# Adc.net
KiCad netlist of a schematic drawn in EAGLE
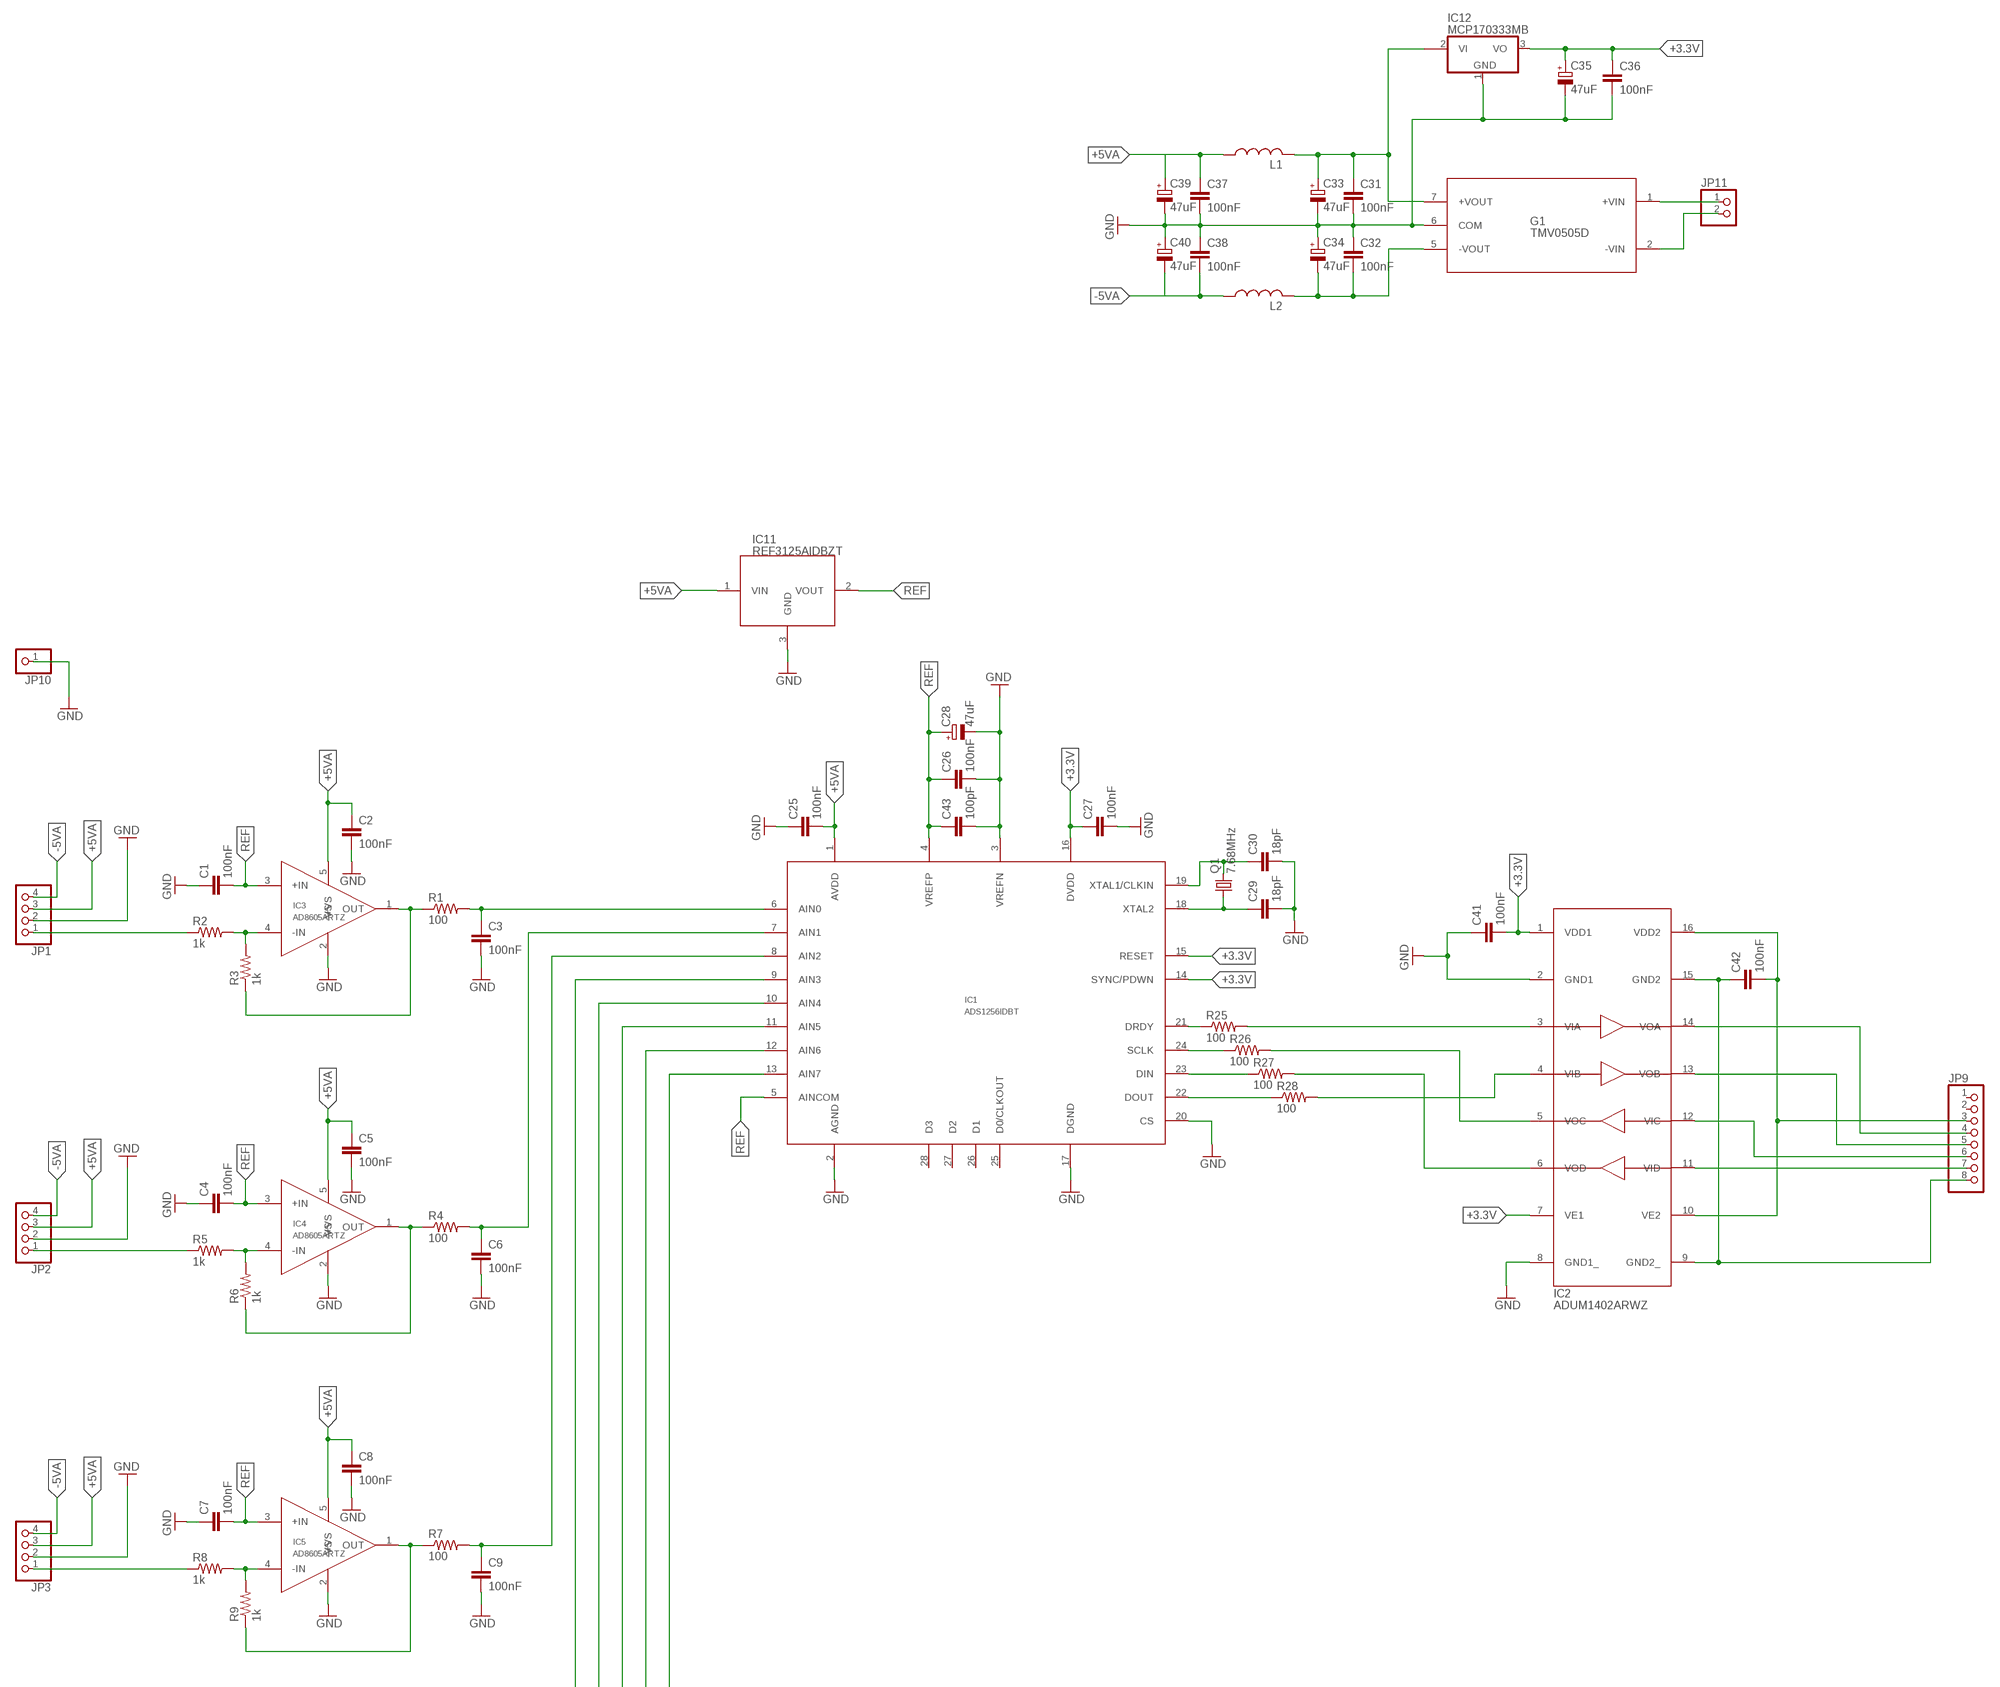
[diagram p0: schematic, sheet 1, part 1 of 2]
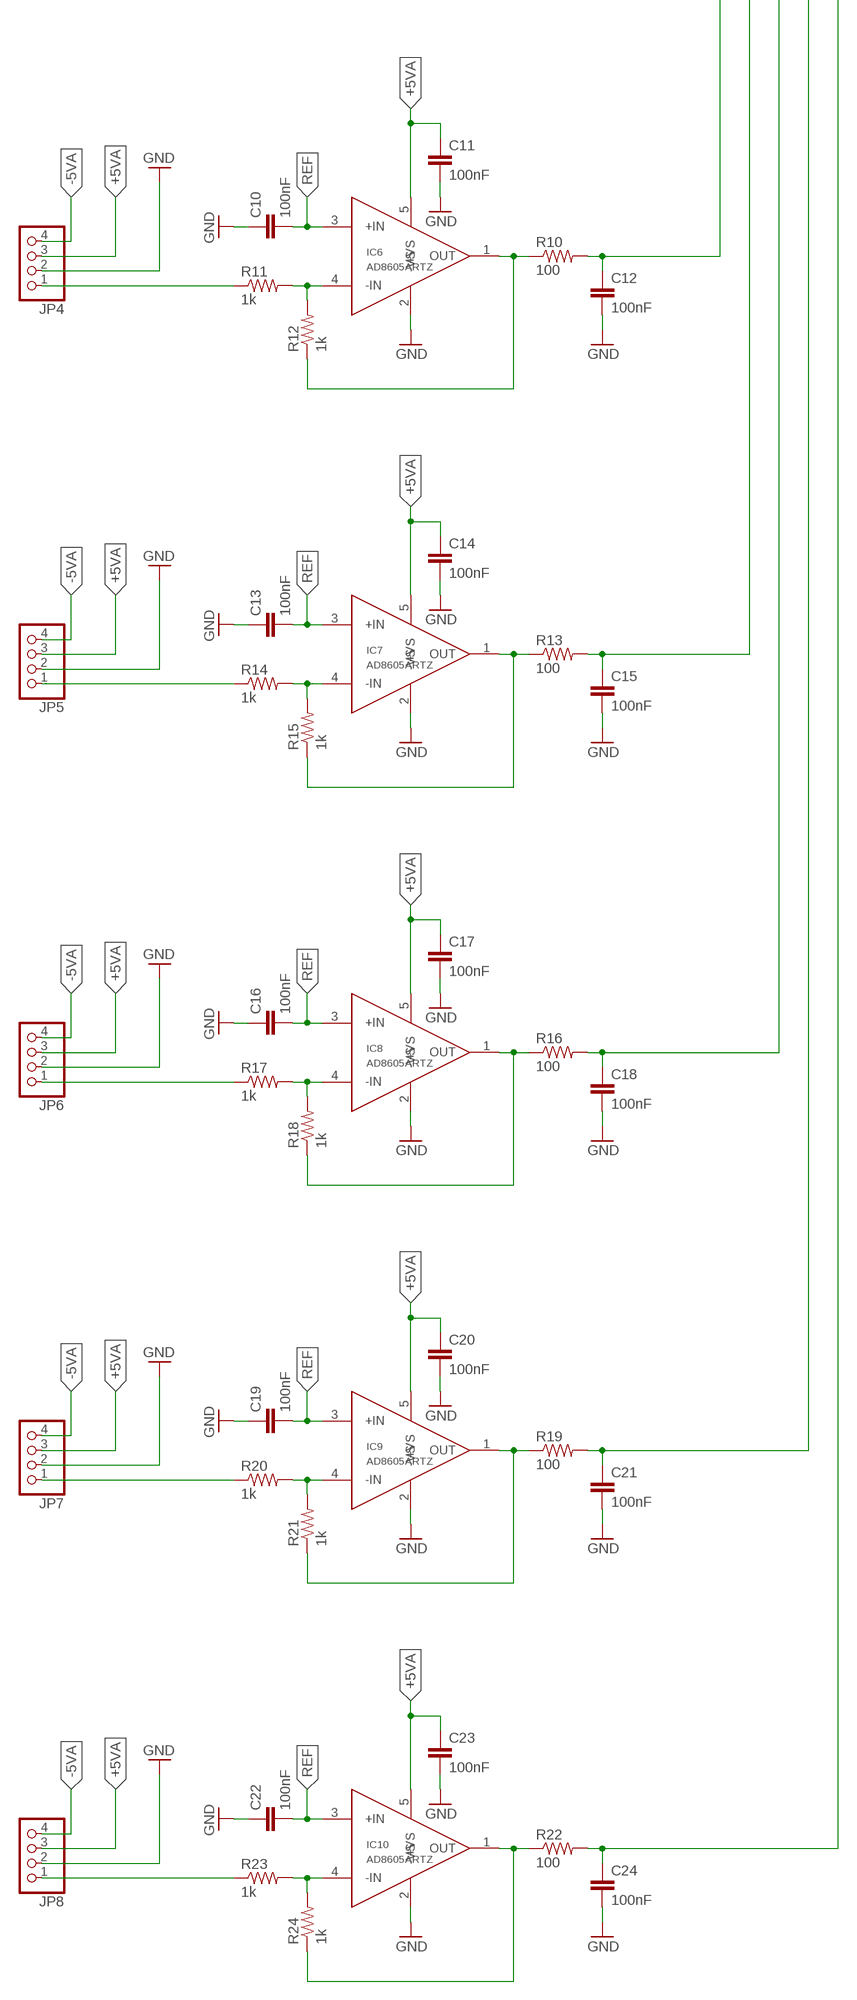
[diagram p1: schematic, sheet 1, part 2 of 2]

(export (version "E")
  (design (tool "Eeschema 10.0.6"))
  (components
    (comp (ref "C1")
      (value "100nF")
      (footprint "eagle-import:0805")
      (libsource (lib "eagle-import") (part "CAP0805"))
    )
    (comp (ref "C2")
      (value "100nF")
      (footprint "eagle-import:0805")
      (libsource (lib "eagle-import") (part "CAP0805"))
    )
    (comp (ref "C3")
      (value "100nF")
      (footprint "eagle-import:0805")
      (libsource (lib "eagle-import") (part "CAP0805"))
    )
    (comp (ref "C4")
      (value "100nF")
      (footprint "eagle-import:0805")
      (libsource (lib "eagle-import") (part "CAP0805"))
    )
    (comp (ref "C5")
      (value "100nF")
      (footprint "eagle-import:0805")
      (libsource (lib "eagle-import") (part "CAP0805"))
    )
    (comp (ref "C6")
      (value "100nF")
      (footprint "eagle-import:0805")
      (libsource (lib "eagle-import") (part "CAP0805"))
    )
    (comp (ref "C7")
      (value "100nF")
      (footprint "eagle-import:0805")
      (libsource (lib "eagle-import") (part "CAP0805"))
    )
    (comp (ref "C8")
      (value "100nF")
      (footprint "eagle-import:0805")
      (libsource (lib "eagle-import") (part "CAP0805"))
    )
    (comp (ref "C9")
      (value "100nF")
      (footprint "eagle-import:0805")
      (libsource (lib "eagle-import") (part "CAP0805"))
    )
    (comp (ref "C10")
      (value "100nF")
      (footprint "eagle-import:0805")
      (libsource (lib "eagle-import") (part "CAP0805"))
    )
    (comp (ref "C11")
      (value "100nF")
      (footprint "eagle-import:0805")
      (libsource (lib "eagle-import") (part "CAP0805"))
    )
    (comp (ref "C12")
      (value "100nF")
      (footprint "eagle-import:0805")
      (libsource (lib "eagle-import") (part "CAP0805"))
    )
    (comp (ref "C13")
      (value "100nF")
      (footprint "eagle-import:0805")
      (libsource (lib "eagle-import") (part "CAP0805"))
    )
    (comp (ref "C14")
      (value "100nF")
      (footprint "eagle-import:0805")
      (libsource (lib "eagle-import") (part "CAP0805"))
    )
    (comp (ref "C15")
      (value "100nF")
      (footprint "eagle-import:0805")
      (libsource (lib "eagle-import") (part "CAP0805"))
    )
    (comp (ref "C16")
      (value "100nF")
      (footprint "eagle-import:0805")
      (libsource (lib "eagle-import") (part "CAP0805"))
    )
    (comp (ref "C17")
      (value "100nF")
      (footprint "eagle-import:0805")
      (libsource (lib "eagle-import") (part "CAP0805"))
    )
    (comp (ref "C18")
      (value "100nF")
      (footprint "eagle-import:0805")
      (libsource (lib "eagle-import") (part "CAP0805"))
    )
    (comp (ref "C19")
      (value "100nF")
      (footprint "eagle-import:0805")
      (libsource (lib "eagle-import") (part "CAP0805"))
    )
    (comp (ref "C20")
      (value "100nF")
      (footprint "eagle-import:0805")
      (libsource (lib "eagle-import") (part "CAP0805"))
    )
    (comp (ref "C21")
      (value "100nF")
      (footprint "eagle-import:0805")
      (libsource (lib "eagle-import") (part "CAP0805"))
    )
    (comp (ref "C22")
      (value "100nF")
      (footprint "eagle-import:0805")
      (libsource (lib "eagle-import") (part "CAP0805"))
    )
    (comp (ref "C23")
      (value "100nF")
      (footprint "eagle-import:0805")
      (libsource (lib "eagle-import") (part "CAP0805"))
    )
    (comp (ref "C24")
      (value "100nF")
      (footprint "eagle-import:0805")
      (libsource (lib "eagle-import") (part "CAP0805"))
    )
    (comp (ref "C25")
      (value "100nF")
      (footprint "eagle-import:0805")
      (libsource (lib "eagle-import") (part "CAP0805"))
    )
    (comp (ref "C26")
      (value "100nF")
      (footprint "eagle-import:0805")
      (libsource (lib "eagle-import") (part "CAP0805"))
    )
    (comp (ref "C27")
      (value "100nF")
      (footprint "eagle-import:0805")
      (libsource (lib "eagle-import") (part "CAP0805"))
    )
    (comp (ref "C28")
      (value "47uF")
      (footprint "eagle-import:E2-4")
      (libsource (lib "eagle-import") (part "CPOL-EUE2-4"))
    )
    (comp (ref "C29")
      (value "18pF")
      (footprint "eagle-import:0805")
      (libsource (lib "eagle-import") (part "CAP0805"))
    )
    (comp (ref "C30")
      (value "18pF")
      (footprint "eagle-import:0805")
      (libsource (lib "eagle-import") (part "CAP0805"))
    )
    (comp (ref "C31")
      (value "100nF")
      (footprint "eagle-import:0805")
      (libsource (lib "eagle-import") (part "CAP0805"))
    )
    (comp (ref "C32")
      (value "100nF")
      (footprint "eagle-import:0805")
      (libsource (lib "eagle-import") (part "CAP0805"))
    )
    (comp (ref "C33")
      (value "47uF")
      (footprint "eagle-import:E2-4")
      (libsource (lib "eagle-import") (part "CPOL-EUE2-4"))
    )
    (comp (ref "C34")
      (value "47uF")
      (footprint "eagle-import:E2-4")
      (libsource (lib "eagle-import") (part "CPOL-EUE2-4"))
    )
    (comp (ref "C35")
      (value "47uF")
      (footprint "eagle-import:E2-4")
      (libsource (lib "eagle-import") (part "CPOL-EUE2-4"))
    )
    (comp (ref "C36")
      (value "100nF")
      (footprint "eagle-import:0805")
      (libsource (lib "eagle-import") (part "CAP0805"))
    )
    (comp (ref "C37")
      (value "100nF")
      (footprint "eagle-import:0805")
      (libsource (lib "eagle-import") (part "CAP0805"))
    )
    (comp (ref "C38")
      (value "100nF")
      (footprint "eagle-import:0805")
      (libsource (lib "eagle-import") (part "CAP0805"))
    )
    (comp (ref "C39")
      (value "47uF")
      (footprint "eagle-import:E2-4")
      (libsource (lib "eagle-import") (part "CPOL-EUE2-4"))
    )
    (comp (ref "C40")
      (value "47uF")
      (footprint "eagle-import:E2-4")
      (libsource (lib "eagle-import") (part "CPOL-EUE2-4"))
    )
    (comp (ref "C41")
      (value "100nF")
      (footprint "eagle-import:0805")
      (libsource (lib "eagle-import") (part "CAP0805"))
    )
    (comp (ref "C42")
      (value "100nF")
      (footprint "eagle-import:0805")
      (libsource (lib "eagle-import") (part "CAP0805"))
    )
    (comp (ref "C43")
      (value "100pF")
      (footprint "eagle-import:0805")
      (libsource (lib "eagle-import") (part "CAP0805"))
    )
    (comp (ref "G1")
      (value "TMV0505D")
      (footprint "eagle-import:TMV0505D")
      (libsource (lib "eagle-import") (part "TMV0505D"))
    )
    (comp (ref "IC1")
      (value "ADS1256IDBT")
      (footprint "eagle-import:ADS1256IDBT")
      (libsource (lib "eagle-import") (part "ADS1256IDBT"))
    )
    (comp (ref "IC2")
      (value "ADUM1402ARWZ")
      (footprint "eagle-import:ADUM1402ARWZ")
      (libsource (lib "eagle-import") (part "ADUM1402ARWZ"))
    )
    (comp (ref "IC3")
      (value "AD8605ARTZ")
      (footprint "eagle-import:AD8605ARTZ")
      (libsource (lib "eagle-import") (part "AD8605ARTZ"))
    )
    (comp (ref "IC4")
      (value "AD8605ARTZ")
      (footprint "eagle-import:AD8605ARTZ")
      (libsource (lib "eagle-import") (part "AD8605ARTZ"))
    )
    (comp (ref "IC5")
      (value "AD8605ARTZ")
      (footprint "eagle-import:AD8605ARTZ")
      (libsource (lib "eagle-import") (part "AD8605ARTZ"))
    )
    (comp (ref "IC6")
      (value "AD8605ARTZ")
      (footprint "eagle-import:AD8605ARTZ")
      (libsource (lib "eagle-import") (part "AD8605ARTZ"))
    )
    (comp (ref "IC7")
      (value "AD8605ARTZ")
      (footprint "eagle-import:AD8605ARTZ")
      (libsource (lib "eagle-import") (part "AD8605ARTZ"))
    )
    (comp (ref "IC8")
      (value "AD8605ARTZ")
      (footprint "eagle-import:AD8605ARTZ")
      (libsource (lib "eagle-import") (part "AD8605ARTZ"))
    )
    (comp (ref "IC9")
      (value "AD8605ARTZ")
      (footprint "eagle-import:AD8605ARTZ")
      (libsource (lib "eagle-import") (part "AD8605ARTZ"))
    )
    (comp (ref "IC10")
      (value "AD8605ARTZ")
      (footprint "eagle-import:AD8605ARTZ")
      (libsource (lib "eagle-import") (part "AD8605ARTZ"))
    )
    (comp (ref "IC11")
      (value "REF3125AIDBZT")
      (footprint "eagle-import:REF3125AIDBZT")
      (libsource (lib "eagle-import") (part "REF3125AIDBZT"))
    )
    (comp (ref "IC12")
      (value "MCP170333MB")
      (footprint "eagle-import:SOT89")
      (libsource (lib "eagle-import") (part "MCP1703MB33"))
    )
    (comp (ref "JP1")
      (value "PINHD-1X4")
      (footprint "eagle-import:1X04")
      (libsource (lib "eagle-import") (part "PINHD-1X4"))
    )
    (comp (ref "JP2")
      (value "PINHD-1X4")
      (footprint "eagle-import:1X04")
      (libsource (lib "eagle-import") (part "PINHD-1X4"))
    )
    (comp (ref "JP3")
      (value "PINHD-1X4")
      (footprint "eagle-import:1X04")
      (libsource (lib "eagle-import") (part "PINHD-1X4"))
    )
    (comp (ref "JP4")
      (value "PINHD-1X4")
      (footprint "eagle-import:1X04")
      (libsource (lib "eagle-import") (part "PINHD-1X4"))
    )
    (comp (ref "JP5")
      (value "PINHD-1X4")
      (footprint "eagle-import:1X04")
      (libsource (lib "eagle-import") (part "PINHD-1X4"))
    )
    (comp (ref "JP6")
      (value "PINHD-1X4")
      (footprint "eagle-import:1X04")
      (libsource (lib "eagle-import") (part "PINHD-1X4"))
    )
    (comp (ref "JP7")
      (value "PINHD-1X4")
      (footprint "eagle-import:1X04")
      (libsource (lib "eagle-import") (part "PINHD-1X4"))
    )
    (comp (ref "JP8")
      (value "PINHD-1X4")
      (footprint "eagle-import:1X04")
      (libsource (lib "eagle-import") (part "PINHD-1X4"))
    )
    (comp (ref "JP9")
      (value "PINHD-1X8")
      (footprint "eagle-import:1X08")
      (libsource (lib "eagle-import") (part "PINHD-1X8"))
    )
    (comp (ref "JP10")
      (value "PINHD-1X1")
      (footprint "eagle-import:1X01")
      (libsource (lib "eagle-import") (part "PINHD-1X1"))
    )
    (comp (ref "JP11")
      (value "PINHD-1X2")
      (footprint "eagle-import:1X02")
      (libsource (lib "eagle-import") (part "PINHD-1X2"))
    )
    (comp (ref "L1")
      (value "L-USL4532P")
      (footprint "eagle-import:L4532P")
      (libsource (lib "eagle-import") (part "L-USL4532P"))
    )
    (comp (ref "L2")
      (value "L-USL4532P")
      (footprint "eagle-import:L4532P")
      (libsource (lib "eagle-import") (part "L-USL4532P"))
    )
    (comp (ref "Q1")
      (value "7.68MHz")
      (footprint "eagle-import:HC49U-V")
      (libsource (lib "eagle-import") (part "CRYSTALHC49U-V"))
    )
    (comp (ref "R1")
      (value "100")
      (footprint "eagle-import:0805")
      (libsource (lib "eagle-import") (part "RESISTOR0805-RES"))
    )
    (comp (ref "R2")
      (value "1k")
      (footprint "eagle-import:0805")
      (libsource (lib "eagle-import") (part "RESISTOR0805-RES"))
    )
    (comp (ref "R3")
      (value "1k")
      (footprint "eagle-import:0805")
      (libsource (lib "eagle-import") (part "RESISTOR0805-RES"))
    )
    (comp (ref "R4")
      (value "100")
      (footprint "eagle-import:0805")
      (libsource (lib "eagle-import") (part "RESISTOR0805-RES"))
    )
    (comp (ref "R5")
      (value "1k")
      (footprint "eagle-import:0805")
      (libsource (lib "eagle-import") (part "RESISTOR0805-RES"))
    )
    (comp (ref "R6")
      (value "1k")
      (footprint "eagle-import:0805")
      (libsource (lib "eagle-import") (part "RESISTOR0805-RES"))
    )
    (comp (ref "R7")
      (value "100")
      (footprint "eagle-import:0805")
      (libsource (lib "eagle-import") (part "RESISTOR0805-RES"))
    )
    (comp (ref "R8")
      (value "1k")
      (footprint "eagle-import:0805")
      (libsource (lib "eagle-import") (part "RESISTOR0805-RES"))
    )
    (comp (ref "R9")
      (value "1k")
      (footprint "eagle-import:0805")
      (libsource (lib "eagle-import") (part "RESISTOR0805-RES"))
    )
    (comp (ref "R10")
      (value "100")
      (footprint "eagle-import:0805")
      (libsource (lib "eagle-import") (part "RESISTOR0805-RES"))
    )
    (comp (ref "R11")
      (value "1k")
      (footprint "eagle-import:0805")
      (libsource (lib "eagle-import") (part "RESISTOR0805-RES"))
    )
    (comp (ref "R12")
      (value "1k")
      (footprint "eagle-import:0805")
      (libsource (lib "eagle-import") (part "RESISTOR0805-RES"))
    )
    (comp (ref "R13")
      (value "100")
      (footprint "eagle-import:0805")
      (libsource (lib "eagle-import") (part "RESISTOR0805-RES"))
    )
    (comp (ref "R14")
      (value "1k")
      (footprint "eagle-import:0805")
      (libsource (lib "eagle-import") (part "RESISTOR0805-RES"))
    )
    (comp (ref "R15")
      (value "1k")
      (footprint "eagle-import:0805")
      (libsource (lib "eagle-import") (part "RESISTOR0805-RES"))
    )
    (comp (ref "R16")
      (value "100")
      (footprint "eagle-import:0805")
      (libsource (lib "eagle-import") (part "RESISTOR0805-RES"))
    )
    (comp (ref "R17")
      (value "1k")
      (footprint "eagle-import:0805")
      (libsource (lib "eagle-import") (part "RESISTOR0805-RES"))
    )
    (comp (ref "R18")
      (value "1k")
      (footprint "eagle-import:0805")
      (libsource (lib "eagle-import") (part "RESISTOR0805-RES"))
    )
    (comp (ref "R19")
      (value "100")
      (footprint "eagle-import:0805")
      (libsource (lib "eagle-import") (part "RESISTOR0805-RES"))
    )
    (comp (ref "R20")
      (value "1k")
      (footprint "eagle-import:0805")
      (libsource (lib "eagle-import") (part "RESISTOR0805-RES"))
    )
    (comp (ref "R21")
      (value "1k")
      (footprint "eagle-import:0805")
      (libsource (lib "eagle-import") (part "RESISTOR0805-RES"))
    )
    (comp (ref "R22")
      (value "100")
      (footprint "eagle-import:0805")
      (libsource (lib "eagle-import") (part "RESISTOR0805-RES"))
    )
    (comp (ref "R23")
      (value "1k")
      (footprint "eagle-import:0805")
      (libsource (lib "eagle-import") (part "RESISTOR0805-RES"))
    )
    (comp (ref "R24")
      (value "1k")
      (footprint "eagle-import:0805")
      (libsource (lib "eagle-import") (part "RESISTOR0805-RES"))
    )
    (comp (ref "R25")
      (value "100")
      (footprint "eagle-import:0805")
      (libsource (lib "eagle-import") (part "RESISTOR0805-RES"))
    )
    (comp (ref "R26")
      (value "100")
      (footprint "eagle-import:0805")
      (libsource (lib "eagle-import") (part "RESISTOR0805-RES"))
    )
    (comp (ref "R27")
      (value "100")
      (footprint "eagle-import:0805")
      (libsource (lib "eagle-import") (part "RESISTOR0805-RES"))
    )
    (comp (ref "R28")
      (value "100")
      (footprint "eagle-import:0805")
      (libsource (lib "eagle-import") (part "RESISTOR0805-RES"))
    )
  )
  (nets
    (net (code "1") (name "+3.3V") (class "Default")
      (node (ref "C27") (pin "1") (pinfunction "1_1") (pintype "passive"))
      (node (ref "C35") (pin "+") (pinfunction "+_+") (pintype "passive"))
      (node (ref "C36") (pin "1") (pinfunction "1_1") (pintype "passive"))
      (node (ref "C41") (pin "2") (pinfunction "2_2") (pintype "passive"))
      (node (ref "IC1") (pin "14") (pinfunction "SYNC/PDWN_14") (pintype "bidirectional"))
      (node (ref "IC1") (pin "15") (pinfunction "RESET_15") (pintype "bidirectional"))
      (node (ref "IC1") (pin "16") (pinfunction "DVDD_16") (pintype "bidirectional"))
      (node (ref "IC12") (pin "3") (pinfunction "VO_3") (pintype "passive"))
      (node (ref "IC2") (pin "1") (pinfunction "VDD1_1") (pintype "bidirectional"))
      (node (ref "IC2") (pin "7") (pinfunction "VE1_7") (pintype "bidirectional"))
    )
    (net (code "2") (name "+5VA") (class "Default")
      (node (ref "C11") (pin "1") (pinfunction "1_1") (pintype "passive"))
      (node (ref "C14") (pin "1") (pinfunction "1_1") (pintype "passive"))
      (node (ref "C17") (pin "1") (pinfunction "1_1") (pintype "passive"))
      (node (ref "C2") (pin "1") (pinfunction "1_1") (pintype "passive"))
      (node (ref "C20") (pin "1") (pinfunction "1_1") (pintype "passive"))
      (node (ref "C23") (pin "1") (pinfunction "1_1") (pintype "passive"))
      (node (ref "C25") (pin "2") (pinfunction "2_2") (pintype "passive"))
      (node (ref "C37") (pin "1") (pinfunction "1_1") (pintype "passive"))
      (node (ref "C39") (pin "+") (pinfunction "+_+") (pintype "passive"))
      (node (ref "C5") (pin "1") (pinfunction "1_1") (pintype "passive"))
      (node (ref "C8") (pin "1") (pinfunction "1_1") (pintype "passive"))
      (node (ref "IC1") (pin "1") (pinfunction "AVDD_1") (pintype "bidirectional"))
      (node (ref "IC10") (pin "5") (pinfunction "+VS_5") (pintype "power_in"))
      (node (ref "IC11") (pin "1") (pinfunction "VIN_1") (pintype "bidirectional"))
      (node (ref "IC3") (pin "5") (pinfunction "+VS_5") (pintype "power_in"))
      (node (ref "IC4") (pin "5") (pinfunction "+VS_5") (pintype "power_in"))
      (node (ref "IC5") (pin "5") (pinfunction "+VS_5") (pintype "power_in"))
      (node (ref "IC6") (pin "5") (pinfunction "+VS_5") (pintype "power_in"))
      (node (ref "IC7") (pin "5") (pinfunction "+VS_5") (pintype "power_in"))
      (node (ref "IC8") (pin "5") (pinfunction "+VS_5") (pintype "power_in"))
      (node (ref "IC9") (pin "5") (pinfunction "+VS_5") (pintype "power_in"))
      (node (ref "JP1") (pin "3") (pinfunction "3_3") (pintype "passive"))
      (node (ref "JP2") (pin "3") (pinfunction "3_3") (pintype "passive"))
      (node (ref "JP3") (pin "3") (pinfunction "3_3") (pintype "passive"))
      (node (ref "JP4") (pin "3") (pinfunction "3_3") (pintype "passive"))
      (node (ref "JP5") (pin "3") (pinfunction "3_3") (pintype "passive"))
      (node (ref "JP6") (pin "3") (pinfunction "3_3") (pintype "passive"))
      (node (ref "JP7") (pin "3") (pinfunction "3_3") (pintype "passive"))
      (node (ref "JP8") (pin "3") (pinfunction "3_3") (pintype "passive"))
      (node (ref "L1") (pin "1") (pinfunction "1_1") (pintype "passive"))
    )
    (net (code "3") (name "-5VA") (class "Default")
      (node (ref "C38") (pin "2") (pinfunction "2_2") (pintype "passive"))
      (node (ref "C40") (pin "-") (pinfunction "-_-") (pintype "passive"))
      (node (ref "JP1") (pin "4") (pinfunction "4_4") (pintype "passive"))
      (node (ref "JP2") (pin "4") (pinfunction "4_4") (pintype "passive"))
      (node (ref "JP3") (pin "4") (pinfunction "4_4") (pintype "passive"))
      (node (ref "JP4") (pin "4") (pinfunction "4_4") (pintype "passive"))
      (node (ref "JP5") (pin "4") (pinfunction "4_4") (pintype "passive"))
      (node (ref "JP6") (pin "4") (pinfunction "4_4") (pintype "passive"))
      (node (ref "JP7") (pin "4") (pinfunction "4_4") (pintype "passive"))
      (node (ref "JP8") (pin "4") (pinfunction "4_4") (pintype "passive"))
      (node (ref "L2") (pin "1") (pinfunction "1_1") (pintype "passive"))
    )
    (net (code "4") (name "GND") (class "Default")
      (node (ref "C1") (pin "1") (pinfunction "1_1") (pintype "passive"))
      (node (ref "C10") (pin "1") (pinfunction "1_1") (pintype "passive"))
      (node (ref "C11") (pin "2") (pinfunction "2_2") (pintype "passive"))
      (node (ref "C12") (pin "2") (pinfunction "2_2") (pintype "passive"))
      (node (ref "C13") (pin "1") (pinfunction "1_1") (pintype "passive"))
      (node (ref "C14") (pin "2") (pinfunction "2_2") (pintype "passive"))
      (node (ref "C15") (pin "2") (pinfunction "2_2") (pintype "passive"))
      (node (ref "C16") (pin "1") (pinfunction "1_1") (pintype "passive"))
      (node (ref "C17") (pin "2") (pinfunction "2_2") (pintype "passive"))
      (node (ref "C18") (pin "2") (pinfunction "2_2") (pintype "passive"))
      (node (ref "C19") (pin "1") (pinfunction "1_1") (pintype "passive"))
      (node (ref "C2") (pin "2") (pinfunction "2_2") (pintype "passive"))
      (node (ref "C20") (pin "2") (pinfunction "2_2") (pintype "passive"))
      (node (ref "C21") (pin "2") (pinfunction "2_2") (pintype "passive"))
      (node (ref "C22") (pin "1") (pinfunction "1_1") (pintype "passive"))
      (node (ref "C23") (pin "2") (pinfunction "2_2") (pintype "passive"))
      (node (ref "C24") (pin "2") (pinfunction "2_2") (pintype "passive"))
      (node (ref "C25") (pin "1") (pinfunction "1_1") (pintype "passive"))
      (node (ref "C26") (pin "2") (pinfunction "2_2") (pintype "passive"))
      (node (ref "C27") (pin "2") (pinfunction "2_2") (pintype "passive"))
      (node (ref "C28") (pin "-") (pinfunction "-_-") (pintype "passive"))
      (node (ref "C29") (pin "2") (pinfunction "2_2") (pintype "passive"))
      (node (ref "C3") (pin "2") (pinfunction "2_2") (pintype "passive"))
      (node (ref "C30") (pin "2") (pinfunction "2_2") (pintype "passive"))
      (node (ref "C31") (pin "2") (pinfunction "2_2") (pintype "passive"))
      (node (ref "C32") (pin "1") (pinfunction "1_1") (pintype "passive"))
      (node (ref "C33") (pin "-") (pinfunction "-_-") (pintype "passive"))
      (node (ref "C34") (pin "+") (pinfunction "+_+") (pintype "passive"))
      (node (ref "C35") (pin "-") (pinfunction "-_-") (pintype "passive"))
      (node (ref "C36") (pin "2") (pinfunction "2_2") (pintype "passive"))
      (node (ref "C37") (pin "2") (pinfunction "2_2") (pintype "passive"))
      (node (ref "C38") (pin "1") (pinfunction "1_1") (pintype "passive"))
      (node (ref "C39") (pin "-") (pinfunction "-_-") (pintype "passive"))
      (node (ref "C4") (pin "1") (pinfunction "1_1") (pintype "passive"))
      (node (ref "C40") (pin "+") (pinfunction "+_+") (pintype "passive"))
      (node (ref "C41") (pin "1") (pinfunction "1_1") (pintype "passive"))
      (node (ref "C43") (pin "2") (pinfunction "2_2") (pintype "passive"))
      (node (ref "C5") (pin "2") (pinfunction "2_2") (pintype "passive"))
      (node (ref "C6") (pin "2") (pinfunction "2_2") (pintype "passive"))
      (node (ref "C7") (pin "1") (pinfunction "1_1") (pintype "passive"))
      (node (ref "C8") (pin "2") (pinfunction "2_2") (pintype "passive"))
      (node (ref "C9") (pin "2") (pinfunction "2_2") (pintype "passive"))
      (node (ref "G1") (pin "6") (pinfunction "COM_6") (pintype "bidirectional"))
      (node (ref "IC1") (pin "17") (pinfunction "DGND_17") (pintype "bidirectional"))
      (node (ref "IC1") (pin "2") (pinfunction "AGND_2") (pintype "bidirectional"))
      (node (ref "IC1") (pin "20") (pinfunction "CS_20") (pintype "bidirectional"))
      (node (ref "IC1") (pin "3") (pinfunction "VREFN_3") (pintype "bidirectional"))
      (node (ref "IC10") (pin "2") (pinfunction "-VS_2") (pintype "power_in"))
      (node (ref "IC11") (pin "3") (pinfunction "GND_3") (pintype "bidirectional"))
      (node (ref "IC12") (pin "1") (pinfunction "GND_1") (pintype "passive"))
      (node (ref "IC2") (pin "2") (pinfunction "GND1_2") (pintype "bidirectional"))
      (node (ref "IC2") (pin "8") (pinfunction "GND1__8") (pintype "bidirectional"))
      (node (ref "IC3") (pin "2") (pinfunction "-VS_2") (pintype "power_in"))
      (node (ref "IC4") (pin "2") (pinfunction "-VS_2") (pintype "power_in"))
      (node (ref "IC5") (pin "2") (pinfunction "-VS_2") (pintype "power_in"))
      (node (ref "IC6") (pin "2") (pinfunction "-VS_2") (pintype "power_in"))
      (node (ref "IC7") (pin "2") (pinfunction "-VS_2") (pintype "power_in"))
      (node (ref "IC8") (pin "2") (pinfunction "-VS_2") (pintype "power_in"))
      (node (ref "IC9") (pin "2") (pinfunction "-VS_2") (pintype "power_in"))
      (node (ref "JP1") (pin "2") (pinfunction "2_2") (pintype "passive"))
      (node (ref "JP10") (pin "1") (pinfunction "1_1") (pintype "passive"))
      (node (ref "JP2") (pin "2") (pinfunction "2_2") (pintype "passive"))
      (node (ref "JP3") (pin "2") (pinfunction "2_2") (pintype "passive"))
      (node (ref "JP4") (pin "2") (pinfunction "2_2") (pintype "passive"))
      (node (ref "JP5") (pin "2") (pinfunction "2_2") (pintype "passive"))
      (node (ref "JP6") (pin "2") (pinfunction "2_2") (pintype "passive"))
      (node (ref "JP7") (pin "2") (pinfunction "2_2") (pintype "passive"))
      (node (ref "JP8") (pin "2") (pinfunction "2_2") (pintype "passive"))
    )
    (net (code "5") (name "Net-(G1-+VIN)") (class "Default")
      (node (ref "G1") (pin "1") (pinfunction "+VIN_1") (pintype "bidirectional"))
      (node (ref "JP11") (pin "1") (pinfunction "1_1") (pintype "passive"))
    )
    (net (code "6") (name "Net-(G1-+VOUT)") (class "Default")
      (node (ref "C31") (pin "1") (pinfunction "1_1") (pintype "passive"))
      (node (ref "C33") (pin "+") (pinfunction "+_+") (pintype "passive"))
      (node (ref "G1") (pin "7") (pinfunction "+VOUT_7") (pintype "bidirectional"))
      (node (ref "IC12") (pin "2@1") (pinfunction "VI1_2@1") (pintype "input"))
      (node (ref "L1") (pin "2") (pinfunction "2_2") (pintype "passive"))
    )
    (net (code "7") (name "Net-(G1--VIN)") (class "Default")
      (node (ref "G1") (pin "2") (pinfunction "-VIN_2") (pintype "bidirectional"))
      (node (ref "JP11") (pin "2") (pinfunction "2_2") (pintype "passive"))
    )
    (net (code "8") (name "Net-(G1--VOUT)") (class "Default")
      (node (ref "C32") (pin "2") (pinfunction "2_2") (pintype "passive"))
      (node (ref "C34") (pin "-") (pinfunction "-_-") (pintype "passive"))
      (node (ref "G1") (pin "5") (pinfunction "-VOUT_5") (pintype "bidirectional"))
      (node (ref "L2") (pin "2") (pinfunction "2_2") (pintype "passive"))
    )
    (net (code "9") (name "Net-(IC1-AIN0)") (class "Default")
      (node (ref "C3") (pin "1") (pinfunction "1_1") (pintype "passive"))
      (node (ref "IC1") (pin "6") (pinfunction "AIN0_6") (pintype "bidirectional"))
      (node (ref "R1") (pin "2") (pinfunction "2_2") (pintype "passive"))
    )
    (net (code "10") (name "Net-(IC1-AIN1)") (class "Default")
      (node (ref "C6") (pin "1") (pinfunction "1_1") (pintype "passive"))
      (node (ref "IC1") (pin "7") (pinfunction "AIN1_7") (pintype "bidirectional"))
      (node (ref "R4") (pin "2") (pinfunction "2_2") (pintype "passive"))
    )
    (net (code "11") (name "Net-(IC1-AIN2)") (class "Default")
      (node (ref "C9") (pin "1") (pinfunction "1_1") (pintype "passive"))
      (node (ref "IC1") (pin "8") (pinfunction "AIN2_8") (pintype "bidirectional"))
      (node (ref "R7") (pin "2") (pinfunction "2_2") (pintype "passive"))
    )
    (net (code "12") (name "Net-(IC1-AIN3)") (class "Default")
      (node (ref "C12") (pin "1") (pinfunction "1_1") (pintype "passive"))
      (node (ref "IC1") (pin "9") (pinfunction "AIN3_9") (pintype "bidirectional"))
      (node (ref "R10") (pin "2") (pinfunction "2_2") (pintype "passive"))
    )
    (net (code "13") (name "Net-(IC1-AIN4)") (class "Default")
      (node (ref "C15") (pin "1") (pinfunction "1_1") (pintype "passive"))
      (node (ref "IC1") (pin "10") (pinfunction "AIN4_10") (pintype "bidirectional"))
      (node (ref "R13") (pin "2") (pinfunction "2_2") (pintype "passive"))
    )
    (net (code "14") (name "Net-(IC1-AIN5)") (class "Default")
      (node (ref "C18") (pin "1") (pinfunction "1_1") (pintype "passive"))
      (node (ref "IC1") (pin "11") (pinfunction "AIN5_11") (pintype "bidirectional"))
      (node (ref "R16") (pin "2") (pinfunction "2_2") (pintype "passive"))
    )
    (net (code "15") (name "Net-(IC1-AIN6)") (class "Default")
      (node (ref "C21") (pin "1") (pinfunction "1_1") (pintype "passive"))
      (node (ref "IC1") (pin "12") (pinfunction "AIN6_12") (pintype "bidirectional"))
      (node (ref "R19") (pin "2") (pinfunction "2_2") (pintype "passive"))
    )
    (net (code "16") (name "Net-(IC1-AIN7)") (class "Default")
      (node (ref "C24") (pin "1") (pinfunction "1_1") (pintype "passive"))
      (node (ref "IC1") (pin "13") (pinfunction "AIN7_13") (pintype "bidirectional"))
      (node (ref "R22") (pin "2") (pinfunction "2_2") (pintype "passive"))
    )
    (net (code "17") (name "Net-(IC1-DIN)") (class "Default")
      (node (ref "IC1") (pin "23") (pinfunction "DIN_23") (pintype "bidirectional"))
      (node (ref "R27") (pin "1") (pinfunction "1_1") (pintype "passive"))
    )
    (net (code "18") (name "Net-(IC1-DOUT)") (class "Default")
      (node (ref "IC1") (pin "22") (pinfunction "DOUT_22") (pintype "bidirectional"))
      (node (ref "R28") (pin "1") (pinfunction "1_1") (pintype "passive"))
    )
    (net (code "19") (name "Net-(IC1-DRDY)") (class "Default")
      (node (ref "IC1") (pin "21") (pinfunction "DRDY_21") (pintype "bidirectional"))
      (node (ref "R25") (pin "1") (pinfunction "1_1") (pintype "passive"))
    )
    (net (code "20") (name "Net-(IC1-SCLK)") (class "Default")
      (node (ref "IC1") (pin "24") (pinfunction "SCLK_24") (pintype "bidirectional"))
      (node (ref "R26") (pin "1") (pinfunction "1_1") (pintype "passive"))
    )
    (net (code "21") (name "Net-(IC1-XTAL1{slash}CLKIN)") (class "Default")
      (node (ref "C30") (pin "1") (pinfunction "1_1") (pintype "passive"))
      (node (ref "IC1") (pin "19") (pinfunction "XTAL1/CLKIN_19") (pintype "bidirectional"))
      (node (ref "Q1") (pin "2") (pinfunction "2_2") (pintype "passive"))
    )
    (net (code "22") (name "Net-(IC1-XTAL2)") (class "Default")
      (node (ref "C29") (pin "1") (pinfunction "1_1") (pintype "passive"))
      (node (ref "IC1") (pin "18") (pinfunction "XTAL2_18") (pintype "bidirectional"))
      (node (ref "Q1") (pin "1") (pinfunction "1_1") (pintype "passive"))
    )
    (net (code "23") (name "Net-(IC2-GND2)") (class "Default")
      (node (ref "C42") (pin "1") (pinfunction "1_1") (pintype "passive"))
      (node (ref "IC2") (pin "15") (pinfunction "GND2_15") (pintype "bidirectional"))
      (node (ref "IC2") (pin "9") (pinfunction "GND2__9") (pintype "bidirectional"))
      (node (ref "JP9") (pin "8") (pinfunction "8_8") (pintype "passive"))
    )
    (net (code "24") (name "Net-(IC2-VDD2)") (class "Default")
      (node (ref "C42") (pin "2") (pinfunction "2_2") (pintype "passive"))
      (node (ref "IC2") (pin "10") (pinfunction "VE2_10") (pintype "bidirectional"))
      (node (ref "IC2") (pin "16") (pinfunction "VDD2_16") (pintype "bidirectional"))
      (node (ref "JP9") (pin "3") (pinfunction "3_3") (pintype "passive"))
    )
    (net (code "25") (name "Net-(IC2-VIA)") (class "Default")
      (node (ref "IC2") (pin "3") (pinfunction "VIA_3") (pintype "bidirectional"))
      (node (ref "R25") (pin "2") (pinfunction "2_2") (pintype "passive"))
    )
    (net (code "26") (name "Net-(IC2-VIB)") (class "Default")
      (node (ref "IC2") (pin "4") (pinfunction "VIB_4") (pintype "bidirectional"))
      (node (ref "R28") (pin "2") (pinfunction "2_2") (pintype "passive"))
    )
    (net (code "27") (name "Net-(IC2-VIC)") (class "Default")
      (node (ref "IC2") (pin "12") (pinfunction "VIC_12") (pintype "bidirectional"))
      (node (ref "JP9") (pin "6") (pinfunction "6_6") (pintype "passive"))
    )
    (net (code "28") (name "Net-(IC2-VID)") (class "Default")
      (node (ref "IC2") (pin "11") (pinfunction "VID_11") (pintype "bidirectional"))
      (node (ref "JP9") (pin "7") (pinfunction "7_7") (pintype "passive"))
    )
    (net (code "29") (name "Net-(IC2-VOA)") (class "Default")
      (node (ref "IC2") (pin "14") (pinfunction "VOA_14") (pintype "bidirectional"))
      (node (ref "JP9") (pin "4") (pinfunction "4_4") (pintype "passive"))
    )
    (net (code "30") (name "Net-(IC2-VOB)") (class "Default")
      (node (ref "IC2") (pin "13") (pinfunction "VOB_13") (pintype "bidirectional"))
      (node (ref "JP9") (pin "5") (pinfunction "5_5") (pintype "passive"))
    )
    (net (code "31") (name "Net-(IC2-VOC)") (class "Default")
      (node (ref "IC2") (pin "5") (pinfunction "VOC_5") (pintype "bidirectional"))
      (node (ref "R26") (pin "2") (pinfunction "2_2") (pintype "passive"))
    )
    (net (code "32") (name "Net-(IC2-VOD)") (class "Default")
      (node (ref "IC2") (pin "6") (pinfunction "VOD_6") (pintype "bidirectional"))
      (node (ref "R27") (pin "2") (pinfunction "2_2") (pintype "passive"))
    )
    (net (code "33") (name "Net-(IC3--IN)") (class "Default")
      (node (ref "IC3") (pin "4") (pinfunction "-IN_4") (pintype "bidirectional"))
      (node (ref "R2") (pin "2") (pinfunction "2_2") (pintype "passive"))
      (node (ref "R3") (pin "2") (pinfunction "2_2") (pintype "passive"))
    )
    (net (code "34") (name "Net-(IC3-OUT)") (class "Default")
      (node (ref "IC3") (pin "1") (pinfunction "OUT_1") (pintype "bidirectional"))
      (node (ref "R1") (pin "1") (pinfunction "1_1") (pintype "passive"))
      (node (ref "R3") (pin "1") (pinfunction "1_1") (pintype "passive"))
    )
    (net (code "35") (name "Net-(IC4--IN)") (class "Default")
      (node (ref "IC4") (pin "4") (pinfunction "-IN_4") (pintype "bidirectional"))
      (node (ref "R5") (pin "2") (pinfunction "2_2") (pintype "passive"))
      (node (ref "R6") (pin "2") (pinfunction "2_2") (pintype "passive"))
    )
    (net (code "36") (name "Net-(IC4-OUT)") (class "Default")
      (node (ref "IC4") (pin "1") (pinfunction "OUT_1") (pintype "bidirectional"))
      (node (ref "R4") (pin "1") (pinfunction "1_1") (pintype "passive"))
      (node (ref "R6") (pin "1") (pinfunction "1_1") (pintype "passive"))
    )
    (net (code "37") (name "Net-(IC5--IN)") (class "Default")
      (node (ref "IC5") (pin "4") (pinfunction "-IN_4") (pintype "bidirectional"))
      (node (ref "R8") (pin "2") (pinfunction "2_2") (pintype "passive"))
      (node (ref "R9") (pin "2") (pinfunction "2_2") (pintype "passive"))
    )
    (net (code "38") (name "Net-(IC5-OUT)") (class "Default")
      (node (ref "IC5") (pin "1") (pinfunction "OUT_1") (pintype "bidirectional"))
      (node (ref "R7") (pin "1") (pinfunction "1_1") (pintype "passive"))
      (node (ref "R9") (pin "1") (pinfunction "1_1") (pintype "passive"))
    )
    (net (code "39") (name "Net-(IC6--IN)") (class "Default")
      (node (ref "IC6") (pin "4") (pinfunction "-IN_4") (pintype "bidirectional"))
      (node (ref "R11") (pin "2") (pinfunction "2_2") (pintype "passive"))
      (node (ref "R12") (pin "2") (pinfunction "2_2") (pintype "passive"))
    )
    (net (code "40") (name "Net-(IC6-OUT)") (class "Default")
      (node (ref "IC6") (pin "1") (pinfunction "OUT_1") (pintype "bidirectional"))
      (node (ref "R10") (pin "1") (pinfunction "1_1") (pintype "passive"))
      (node (ref "R12") (pin "1") (pinfunction "1_1") (pintype "passive"))
    )
    (net (code "41") (name "Net-(IC7--IN)") (class "Default")
      (node (ref "IC7") (pin "4") (pinfunction "-IN_4") (pintype "bidirectional"))
      (node (ref "R14") (pin "2") (pinfunction "2_2") (pintype "passive"))
      (node (ref "R15") (pin "2") (pinfunction "2_2") (pintype "passive"))
    )
    (net (code "42") (name "Net-(IC7-OUT)") (class "Default")
      (node (ref "IC7") (pin "1") (pinfunction "OUT_1") (pintype "bidirectional"))
      (node (ref "R13") (pin "1") (pinfunction "1_1") (pintype "passive"))
      (node (ref "R15") (pin "1") (pinfunction "1_1") (pintype "passive"))
    )
    (net (code "43") (name "Net-(IC8--IN)") (class "Default")
      (node (ref "IC8") (pin "4") (pinfunction "-IN_4") (pintype "bidirectional"))
      (node (ref "R17") (pin "2") (pinfunction "2_2") (pintype "passive"))
      (node (ref "R18") (pin "2") (pinfunction "2_2") (pintype "passive"))
    )
    (net (code "44") (name "Net-(IC8-OUT)") (class "Default")
      (node (ref "IC8") (pin "1") (pinfunction "OUT_1") (pintype "bidirectional"))
      (node (ref "R16") (pin "1") (pinfunction "1_1") (pintype "passive"))
      (node (ref "R18") (pin "1") (pinfunction "1_1") (pintype "passive"))
    )
    (net (code "45") (name "Net-(IC9--IN)") (class "Default")
      (node (ref "IC9") (pin "4") (pinfunction "-IN_4") (pintype "bidirectional"))
      (node (ref "R20") (pin "2") (pinfunction "2_2") (pintype "passive"))
      (node (ref "R21") (pin "2") (pinfunction "2_2") (pintype "passive"))
    )
    (net (code "46") (name "Net-(IC9-OUT)") (class "Default")
      (node (ref "IC9") (pin "1") (pinfunction "OUT_1") (pintype "bidirectional"))
      (node (ref "R19") (pin "1") (pinfunction "1_1") (pintype "passive"))
      (node (ref "R21") (pin "1") (pinfunction "1_1") (pintype "passive"))
    )
    (net (code "47") (name "Net-(IC10--IN)") (class "Default")
      (node (ref "IC10") (pin "4") (pinfunction "-IN_4") (pintype "bidirectional"))
      (node (ref "R23") (pin "2") (pinfunction "2_2") (pintype "passive"))
      (node (ref "R24") (pin "2") (pinfunction "2_2") (pintype "passive"))
    )
    (net (code "48") (name "Net-(IC10-OUT)") (class "Default")
      (node (ref "IC10") (pin "1") (pinfunction "OUT_1") (pintype "bidirectional"))
      (node (ref "R22") (pin "1") (pinfunction "1_1") (pintype "passive"))
      (node (ref "R24") (pin "1") (pinfunction "1_1") (pintype "passive"))
    )
    (net (code "49") (name "Net-(JP1-Pad1)") (class "Default")
      (node (ref "JP1") (pin "1") (pinfunction "1_1") (pintype "passive"))
      (node (ref "R2") (pin "1") (pinfunction "1_1") (pintype "passive"))
    )
    (net (code "50") (name "Net-(JP2-Pad1)") (class "Default")
      (node (ref "JP2") (pin "1") (pinfunction "1_1") (pintype "passive"))
      (node (ref "R5") (pin "1") (pinfunction "1_1") (pintype "passive"))
    )
    (net (code "51") (name "Net-(JP3-Pad1)") (class "Default")
      (node (ref "JP3") (pin "1") (pinfunction "1_1") (pintype "passive"))
      (node (ref "R8") (pin "1") (pinfunction "1_1") (pintype "passive"))
    )
    (net (code "52") (name "Net-(JP4-Pad1)") (class "Default")
      (node (ref "JP4") (pin "1") (pinfunction "1_1") (pintype "passive"))
      (node (ref "R11") (pin "1") (pinfunction "1_1") (pintype "passive"))
    )
    (net (code "53") (name "Net-(JP5-Pad1)") (class "Default")
      (node (ref "JP5") (pin "1") (pinfunction "1_1") (pintype "passive"))
      (node (ref "R14") (pin "1") (pinfunction "1_1") (pintype "passive"))
    )
    (net (code "54") (name "Net-(JP6-Pad1)") (class "Default")
      (node (ref "JP6") (pin "1") (pinfunction "1_1") (pintype "passive"))
      (node (ref "R17") (pin "1") (pinfunction "1_1") (pintype "passive"))
    )
    (net (code "55") (name "Net-(JP7-Pad1)") (class "Default")
      (node (ref "JP7") (pin "1") (pinfunction "1_1") (pintype "passive"))
      (node (ref "R20") (pin "1") (pinfunction "1_1") (pintype "passive"))
    )
    (net (code "56") (name "Net-(JP8-Pad1)") (class "Default")
      (node (ref "JP8") (pin "1") (pinfunction "1_1") (pintype "passive"))
      (node (ref "R23") (pin "1") (pinfunction "1_1") (pintype "passive"))
    )
    (net (code "57") (name "REF") (class "Default")
      (node (ref "C1") (pin "2") (pinfunction "2_2") (pintype "passive"))
      (node (ref "C10") (pin "2") (pinfunction "2_2") (pintype "passive"))
      (node (ref "C13") (pin "2") (pinfunction "2_2") (pintype "passive"))
      (node (ref "C16") (pin "2") (pinfunction "2_2") (pintype "passive"))
      (node (ref "C19") (pin "2") (pinfunction "2_2") (pintype "passive"))
      (node (ref "C22") (pin "2") (pinfunction "2_2") (pintype "passive"))
      (node (ref "C26") (pin "1") (pinfunction "1_1") (pintype "passive"))
      (node (ref "C28") (pin "+") (pinfunction "+_+") (pintype "passive"))
      (node (ref "C4") (pin "2") (pinfunction "2_2") (pintype "passive"))
      (node (ref "C43") (pin "1") (pinfunction "1_1") (pintype "passive"))
      (node (ref "C7") (pin "2") (pinfunction "2_2") (pintype "passive"))
      (node (ref "IC1") (pin "4") (pinfunction "VREFP_4") (pintype "bidirectional"))
      (node (ref "IC1") (pin "5") (pinfunction "AINCOM_5") (pintype "bidirectional"))
      (node (ref "IC10") (pin "3") (pinfunction "+IN_3") (pintype "bidirectional"))
      (node (ref "IC11") (pin "2") (pinfunction "VOUT_2") (pintype "bidirectional"))
      (node (ref "IC3") (pin "3") (pinfunction "+IN_3") (pintype "bidirectional"))
      (node (ref "IC4") (pin "3") (pinfunction "+IN_3") (pintype "bidirectional"))
      (node (ref "IC5") (pin "3") (pinfunction "+IN_3") (pintype "bidirectional"))
      (node (ref "IC6") (pin "3") (pinfunction "+IN_3") (pintype "bidirectional"))
      (node (ref "IC7") (pin "3") (pinfunction "+IN_3") (pintype "bidirectional"))
      (node (ref "IC8") (pin "3") (pinfunction "+IN_3") (pintype "bidirectional"))
      (node (ref "IC9") (pin "3") (pinfunction "+IN_3") (pintype "bidirectional"))
    )
    (net (code "58") (name "unconnected-(IC1-D0{slash}CLKOUT-Pad25)") (class "Default")
      (node (ref "IC1") (pin "25") (pinfunction "D0/CLKOUT_25") (pintype "bidirectional"))
    )
    (net (code "59") (name "unconnected-(IC1-D1-Pad26)") (class "Default")
      (node (ref "IC1") (pin "26") (pinfunction "D1_26") (pintype "bidirectional"))
    )
    (net (code "60") (name "unconnected-(IC1-D2-Pad27)") (class "Default")
      (node (ref "IC1") (pin "27") (pinfunction "D2_27") (pintype "bidirectional"))
    )
    (net (code "61") (name "unconnected-(IC1-D3-Pad28)") (class "Default")
      (node (ref "IC1") (pin "28") (pinfunction "D3_28") (pintype "bidirectional"))
    )
    (net (code "62") (name "unconnected-(IC12-VI-Pad2)") (class "Default")
      (node (ref "IC12") (pin "2") (pinfunction "VI_2") (pintype "input"))
    )
    (net (code "63") (name "unconnected-(JP9-Pad1)") (class "Default")
      (node (ref "JP9") (pin "1") (pinfunction "1_1") (pintype "passive"))
    )
    (net (code "64") (name "unconnected-(JP9-Pad2)") (class "Default")
      (node (ref "JP9") (pin "2") (pinfunction "2_2") (pintype "passive"))
    )
  )
)
